# design.net
KiCad netlist of a schematic drawn in Altium Designer
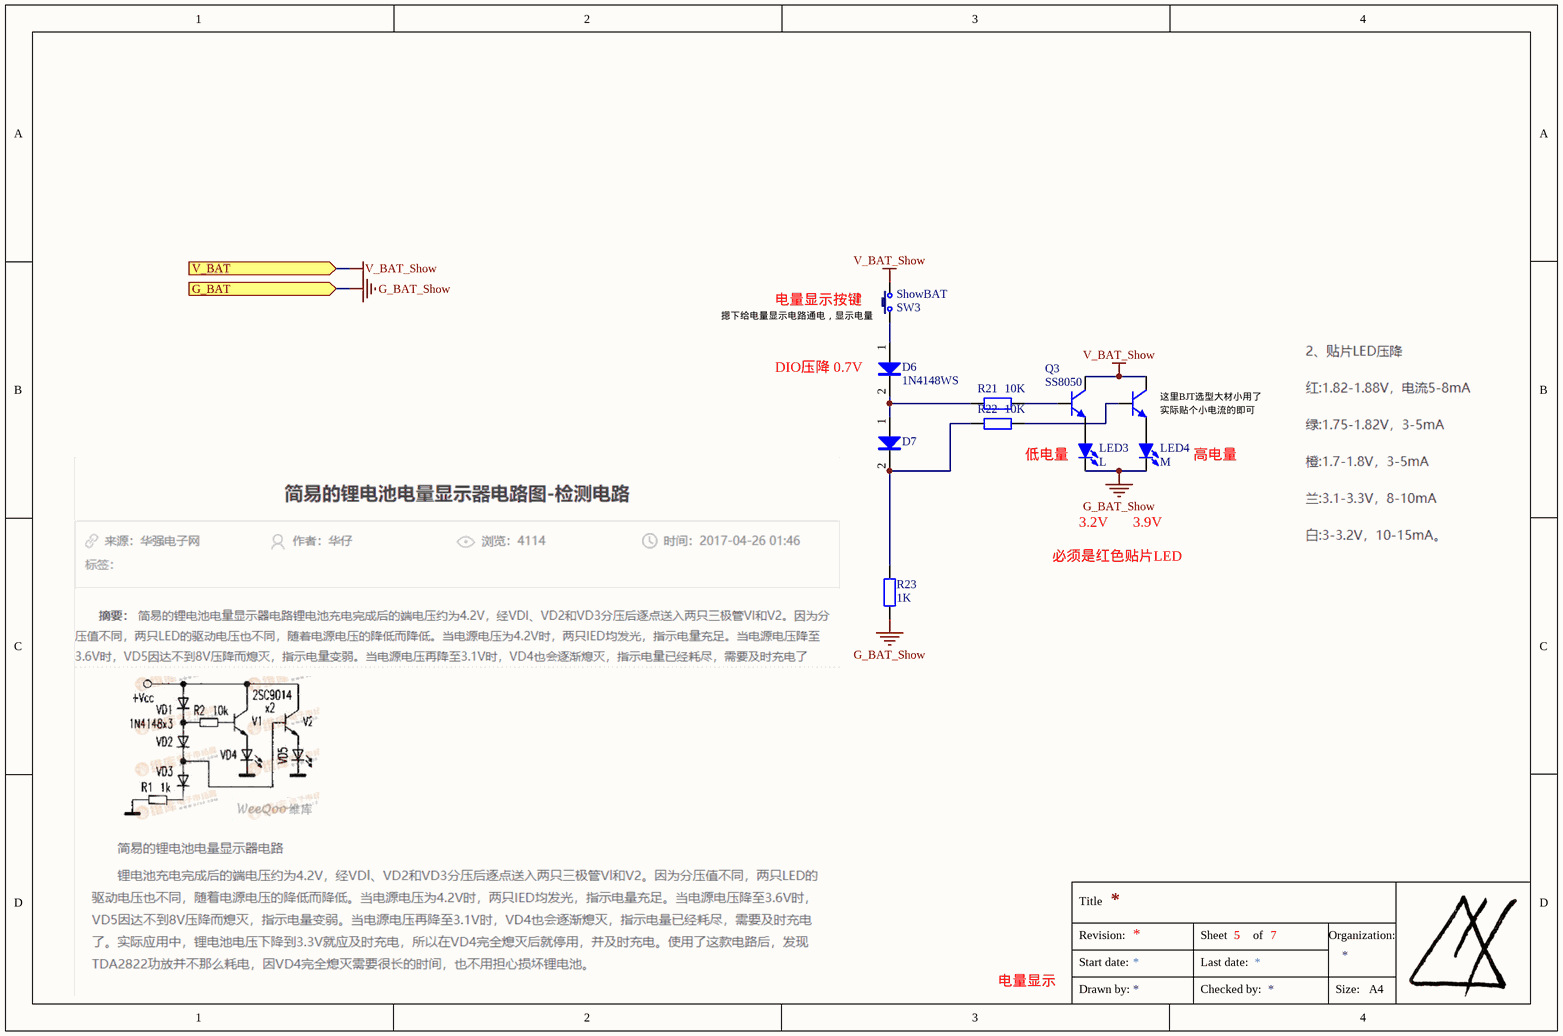
[diagram p0: 锂电池电量显示.SchDoc]

(export (version "E")
  (design (tool "Eeschema 10.0.6"))
  (components
    (comp (ref "D6")
      (value "1N4148WS")
      (footprint "SOD-323")
      (description "高速开关二极管")
      (fields (field (name "版权归属") "源创客"))
      (libsource (lib "8.1   - 二极管-整流桥") (part "1N4148"))
    )
    (comp (ref "D7")
      (value "1N4148WS")
      (footprint "SOD-323")
      (description "高速开关二极管")
      (fields (field (name "版权归属") "源创客"))
      (libsource (lib "8.1   - 二极管-整流桥") (part "1N4148"))
    )
    (comp (ref "LED3")
      (value "L")
      (footprint "LED 0805R")
      (description "贴片LED 红色")
      (fields (field (name "版权归属") "源创客"))
      (libsource (lib "9.1   - LED") (part "LED-SMD"))
    )
    (comp (ref "LED4")
      (value "M")
      (footprint "LED 0805R")
      (description "贴片LED 红色")
      (fields (field (name "版权归属") "源创客"))
      (libsource (lib "9.1   - LED") (part "LED-SMD"))
    )
    (comp (ref "Q3")
      (value "SS8050")
      (footprint "SOT23-3N")
      (description "高频放大-NPN型")
      (fields (field (name "版权归属") "源创客"))
      (libsource (lib "6.2   - 三极管") (part "8050-SMD"))
    )
    (comp (ref "Q4")
      (value "SS8050")
      (footprint "SOT23-3N")
      (description "高频放大-NPN型")
      (fields (field (name "版权归属") "源创客"))
      (libsource (lib "6.2   - 三极管") (part "8050-SMD"))
    )
    (comp (ref "R21")
      (value "10K")
      (footprint "R 0402_L")
      (description "贴片电阻 E-96 1%")
      (libsource (lib "Foundation_temp") (part "R"))
    )
    (comp (ref "R22")
      (value "10K")
      (footprint "R 0402_L")
      (description "贴片电阻 E-96 1%")
      (libsource (lib "Foundation_temp") (part "R"))
    )
    (comp (ref "R23")
      (value "1K")
      (footprint "R 0402_L")
      (description "贴片电阻 E-96 1%")
      (libsource (lib "Foundation_temp") (part "R"))
    )
    (comp (ref "SW3")
      (value "ShowBAT")
      (footprint "TSW DIP-3*6*5_V")
      (description "3x6轻触开关")
      (fields (field (name "版权归属") "源创客"))
      (libsource (lib "5.1   - 按键-开关") (part "TSW 3x6"))
    )
  )
  (nets
    (net (code "1") (name "G_BAT_Show") (class "Default")
      (node (ref "LED3") (pin "2") (pinfunction "K_2") (pintype "passive"))
      (node (ref "LED4") (pin "2") (pinfunction "K_2") (pintype "passive"))
      (node (ref "R23") (pin "2") (pinfunction "2_2") (pintype "passive"))
    )
    (net (code "2") (name "Net-(D6-A)") (class "Default")
      (node (ref "D6") (pin "1") (pinfunction "A_1") (pintype "passive"))
      (node (ref "SW3") (pin "1") (pinfunction "1_1") (pintype "passive"))
    )
    (net (code "3") (name "Net-(D6-K)") (class "Default")
      (node (ref "D6") (pin "2") (pinfunction "K_2") (pintype "passive"))
      (node (ref "D7") (pin "1") (pinfunction "A_1") (pintype "passive"))
      (node (ref "R21") (pin "1") (pinfunction "1_1") (pintype "passive"))
    )
    (net (code "4") (name "Net-(D7-K)") (class "Default")
      (node (ref "D7") (pin "2") (pinfunction "K_2") (pintype "passive"))
      (node (ref "R22") (pin "1") (pinfunction "1_1") (pintype "passive"))
      (node (ref "R23") (pin "1") (pinfunction "1_1") (pintype "passive"))
    )
    (net (code "5") (name "Net-(LED3-A)") (class "Default")
      (node (ref "LED3") (pin "1") (pinfunction "A_1") (pintype "passive"))
      (node (ref "Q3") (pin "2") (pinfunction "E_2") (pintype "passive"))
    )
    (net (code "6") (name "Net-(LED4-A)") (class "Default")
      (node (ref "LED4") (pin "1") (pinfunction "A_1") (pintype "passive"))
      (node (ref "Q4") (pin "2") (pinfunction "E_2") (pintype "passive"))
    )
    (net (code "7") (name "Net-(Q3-B)") (class "Default")
      (node (ref "Q3") (pin "1") (pinfunction "B_1") (pintype "passive"))
      (node (ref "R21") (pin "2") (pinfunction "2_2") (pintype "passive"))
    )
    (net (code "8") (name "Net-(Q4-B)") (class "Default")
      (node (ref "Q4") (pin "1") (pinfunction "B_1") (pintype "passive"))
      (node (ref "R22") (pin "2") (pinfunction "2_2") (pintype "passive"))
    )
    (net (code "9") (name "V_BAT_Show") (class "Default")
      (node (ref "Q3") (pin "3") (pinfunction "C_3") (pintype "passive"))
      (node (ref "Q4") (pin "3") (pinfunction "C_3") (pintype "passive"))
      (node (ref "SW3") (pin "2") (pinfunction "2_2") (pintype "passive"))
    )
  )
)
